# FuenteCapacitiva.net
KiCad netlist of a schematic drawn in Altium Designer
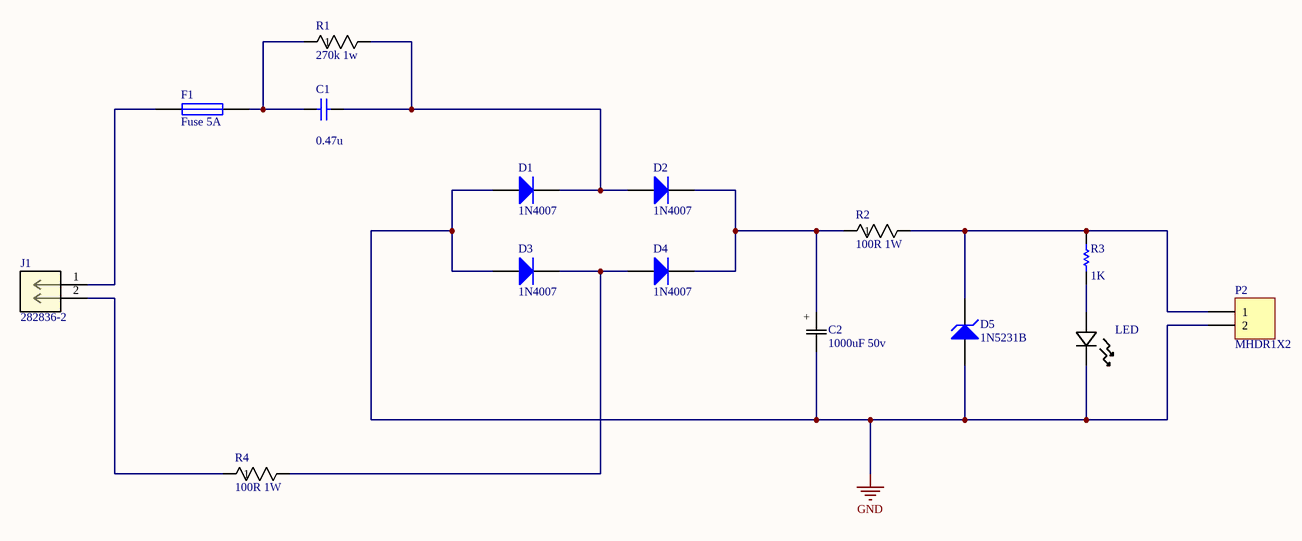
[diagram p0: FuenteCapacitiva.SchDoc]

(export (version "E")
  (design (tool "Eeschema 10.0.6"))
  (components
    (comp (ref "C1")
      (value "0.47u")
      (footprint "Cap470n400v")
      (description "Capacitor")
      (fields (field (name "Comment") "Cap") (field (name "PUBLISHER") "Altium Limited"))
      (libsource (lib "Miscellaneous Devices") (part "Cap"))
    )
    (comp (ref "C2")
      (value "1000uF 50v")
      (footprint "CAP_12.5 X 25")
      (description "Imported")
      (fields (field (name "MANUFACTURER_PART_NUMBER") "UVY1H102MHD"))
      (libsource (lib "AltiumDesigner") (part "UVY1H102MHD"))
    )
    (comp (ref "D1")
      (value "1N4007")
      (footprint "DO-41")
      (description "1.0 Ampere General Purpose Rectifier")
      (fields (field (name "PUBLISHER") "Altium Limited"))
      (libsource (lib "FSC Discrete Rectifier") (part "1N4007"))
    )
    (comp (ref "D2")
      (value "1N4007")
      (footprint "DO-41")
      (description "1.0 Ampere General Purpose Rectifier")
      (fields (field (name "PUBLISHER") "Altium Limited"))
      (libsource (lib "FSC Discrete Rectifier") (part "1N4007"))
    )
    (comp (ref "D3")
      (value "1N4007")
      (footprint "DO-41")
      (description "1.0 Ampere General Purpose Rectifier")
      (fields (field (name "PUBLISHER") "Altium Limited"))
      (libsource (lib "FSC Discrete Rectifier") (part "1N4007"))
    )
    (comp (ref "D4")
      (value "1N4007")
      (footprint "DO-41")
      (description "1.0 Ampere General Purpose Rectifier")
      (fields (field (name "PUBLISHER") "Altium Limited"))
      (libsource (lib "FSC Discrete Rectifier") (part "1N4007"))
    )
    (comp (ref "D5")
      (value "1N5231B")
      (footprint "DO-35")
      (description "Half Watt Zener")
      (fields (field (name "PUBLISHER") "Altium Limited"))
      (libsource (lib "FSC Discrete Diode") (part "1N5231B"))
    )
    (comp (ref "F1")
      (value "Fuse 5A")
      (footprint "PIN-W2/E2.8")
      (description "Fuse")
      (fields (field (name "PUBLISHER") "Altium Limited"))
      (libsource (lib "Miscellaneous Devices") (part "Fuse 1"))
    )
    (comp (ref "J1")
      (value "282836-2")
      (footprint "CONN2_282836-2")
      (description "TERMI-BLOK PCB MOUNT  90 2P.")
      (fields (field (name "COPYRIGHT") "Copyright (C) 2016 Accelerated Designs. All rights reserved"))
      (libsource (lib "AltiumDesigner") (part "282836-2"))
    )
    (comp (ref "LED")
      (value "~")
      (footprint "HLMP")
      (description "Imported")
      (fields (field (name "MANUFACTURER_PART_NUMBER") "HLMP-1301"))
      (libsource (lib "AltiumDesigner") (part "HLMP-1301"))
    )
    (comp (ref "P2")
      (value "MHDR1X2")
      (footprint "MHDR1X2")
      (description "Header, 2-Pin")
      (fields (field (name "PUBLISHER") "Altium Limited"))
      (libsource (lib "Miscellaneous Connectors") (part "MHDR1X2"))
    )
    (comp (ref "R1")
      (value "270k 1w")
      (footprint "PR01")
      (description "Imported")
      (fields (field (name "MANUFACTURER_PART_NUMBER") "PR01000104703JR500"))
      (libsource (lib "AltiumDesigner") (part "PR01000104703JR5"))
    )
    (comp (ref "R2")
      (value "100R 1W")
      (footprint "YAG_FMP100")
      (description "Imported")
      (fields (field (name "MANUFACTURER_PART_NUMBER") "FMP100JR-52-100R"))
      (libsource (lib "AltiumDesigner") (part "FMP100JR-52-100R"))
    )
    (comp (ref "R3")
      (value "1K")
      (footprint "AXIAL-0.3")
      (description "Resistor")
      (fields (field (name "Comment") "Res1") (field (name "PUBLISHER") "Altium Limited"))
      (libsource (lib "Miscellaneous Devices") (part "Res1"))
    )
    (comp (ref "R4")
      (value "100R 1W")
      (footprint "YAG_FMP100")
      (description "Imported")
      (fields (field (name "MANUFACTURER_PART_NUMBER") "FMP100JR-52-100R"))
      (libsource (lib "AltiumDesigner") (part "FMP100JR-52-100R"))
    )
  )
  (nets
    (net (code "1") (name "GND") (class "Default")
      (node (ref "C2") (pin "2") (pinfunction "2_2") (pintype "passive"))
      (node (ref "D1") (pin "1") (pinfunction "A_1") (pintype "passive"))
      (node (ref "D3") (pin "1") (pinfunction "A_1") (pintype "passive"))
      (node (ref "D5") (pin "1") (pinfunction "A_1") (pintype "passive"))
      (node (ref "LED") (pin "1") (pinfunction "1_1") (pintype "passive"))
      (node (ref "P2") (pin "2") (pinfunction "2_2") (pintype "passive"))
    )
    (net (code "2") (name "Net-(C1-Pad1)") (class "Default")
      (node (ref "C1") (pin "1") (pinfunction "1_1") (pintype "passive"))
      (node (ref "F1") (pin "2") (pinfunction "2_2") (pintype "passive"))
      (node (ref "R1") (pin "1") (pinfunction "1_1") (pintype "passive"))
    )
    (net (code "3") (name "Net-(D1-K)") (class "Default")
      (node (ref "C1") (pin "2") (pinfunction "2_2") (pintype "passive"))
      (node (ref "D1") (pin "2") (pinfunction "K_2") (pintype "passive"))
      (node (ref "D2") (pin "1") (pinfunction "A_1") (pintype "passive"))
      (node (ref "R1") (pin "2") (pinfunction "2_2") (pintype "passive"))
    )
    (net (code "4") (name "Net-(D2-K)") (class "Default")
      (node (ref "C2") (pin "1") (pinfunction "1_1") (pintype "passive"))
      (node (ref "D2") (pin "2") (pinfunction "K_2") (pintype "passive"))
      (node (ref "D4") (pin "2") (pinfunction "K_2") (pintype "passive"))
      (node (ref "R2") (pin "1") (pinfunction "1_1") (pintype "passive"))
    )
    (net (code "5") (name "Net-(D3-K)") (class "Default")
      (node (ref "D3") (pin "2") (pinfunction "K_2") (pintype "passive"))
      (node (ref "D4") (pin "1") (pinfunction "A_1") (pintype "passive"))
      (node (ref "R4") (pin "2") (pinfunction "2_2") (pintype "passive"))
    )
    (net (code "6") (name "Net-(D5-K)") (class "Default")
      (node (ref "D5") (pin "2") (pinfunction "K_2") (pintype "passive"))
      (node (ref "P2") (pin "1") (pinfunction "1_1") (pintype "passive"))
      (node (ref "R2") (pin "2") (pinfunction "2_2") (pintype "passive"))
      (node (ref "R3") (pin "1") (pinfunction "1_1") (pintype "passive"))
    )
    (net (code "7") (name "Net-(F1-Pad1)") (class "Default")
      (node (ref "F1") (pin "1") (pinfunction "1_1") (pintype "passive"))
      (node (ref "J1") (pin "1") (pinfunction "1_1") (pintype "passive"))
    )
    (net (code "8") (name "Net-(J1-Pad2)") (class "Default")
      (node (ref "J1") (pin "2") (pinfunction "2_2") (pintype "passive"))
      (node (ref "R4") (pin "1") (pinfunction "1_1") (pintype "passive"))
    )
    (net (code "9") (name "Net-(LED-Pad2)") (class "Default")
      (node (ref "LED") (pin "2") (pinfunction "2_2") (pintype "passive"))
      (node (ref "R3") (pin "2") (pinfunction "2_2") (pintype "passive"))
    )
  )
)
